# design.net
KiCad netlist of a schematic drawn in Altium Designer
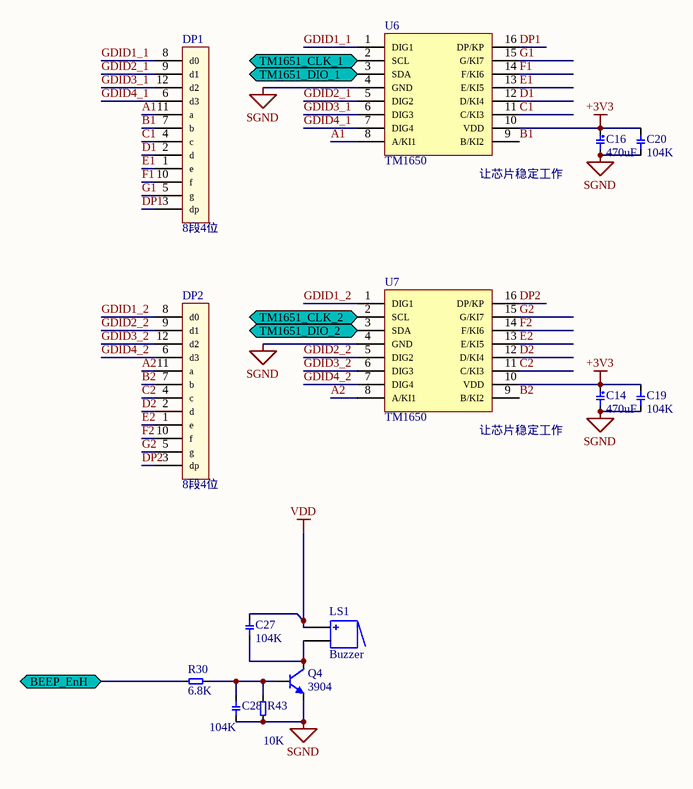
[diagram p0: 用户显示.SchDoc]

(export (version "E")
  (design (tool "Eeschema 10.0.6"))
  (components
    (comp (ref "C14")
      (value "470uF")
      (footprint "电容卧P2.54-D6.3-H7")
      (description "极性电容")
      (fields (field (name "PUBLISHER") "Altium Limited"))
      (libsource (lib "Miscellaneous Devices") (part "Cap Pol"))
    )
    (comp (ref "C16")
      (value "470uF")
      (footprint "电容卧P2.54-D6.3-H7")
      (description "极性电容")
      (fields (field (name "PUBLISHER") "Altium Limited"))
      (libsource (lib "Miscellaneous Devices") (part "Cap Pol"))
    )
    (comp (ref "C19")
      (value "104K")
      (footprint "0603")
      (description "电容")
      (fields (field (name "PUBLISHER") "Altium Limited"))
      (libsource (lib "Miscellaneous Devices") (part "Cap"))
    )
    (comp (ref "C20")
      (value "104K")
      (footprint "0603")
      (description "电容")
      (fields (field (name "PUBLISHER") "Altium Limited"))
      (libsource (lib "Miscellaneous Devices") (part "Cap"))
    )
    (comp (ref "C27")
      (value "104K")
      (footprint "0603")
      (description "电容")
      (fields (field (name "PUBLISHER") "Altium Limited"))
      (libsource (lib "Miscellaneous Devices") (part "Cap"))
    )
    (comp (ref "C28")
      (value "104K")
      (footprint "0603")
      (description "电容")
      (fields (field (name "PUBLISHER") "Altium Limited"))
      (libsource (lib "Miscellaneous Devices") (part "Cap"))
    )
    (comp (ref "DP1")
      (value "8段4位")
      (footprint "数码管0.36英寸")
      (description "数码管4位共阴")
      (libsource (lib "Miscellaneous Devices") (part "数码管4位"))
    )
    (comp (ref "DP2")
      (value "8段4位")
      (footprint "数码管0.36英寸")
      (description "数码管4位共阴")
      (libsource (lib "Miscellaneous Devices") (part "数码管4位"))
    )
    (comp (ref "LS1")
      (value "Buzzer")
      (footprint "蜂鸣器12-95")
      (description "Magnetic Transducer Buzzer")
      (fields (field (name "PUBLISHER") "Altium Limited"))
      (libsource (lib "Miscellaneous Devices") (part "蜂鸣器Buzzer"))
    )
    (comp (ref "Q4")
      (value "3904")
      (footprint "SOT-23-3L")
      (description "三极管")
      (fields (field (name "PUBLISHER") "Altium Limited"))
      (libsource (lib "Miscellaneous Devices") (part "transistor NPN"))
    )
    (comp (ref "R30")
      (value "6.8K")
      (footprint "0603")
      (description "电阻")
      (fields (field (name "PUBLISHER") "Altium Limited"))
      (libsource (lib "Miscellaneous Devices") (part "Res1"))
    )
    (comp (ref "R43")
      (value "10K")
      (footprint "0603")
      (description "电阻")
      (fields (field (name "PUBLISHER") "Altium Limited"))
      (libsource (lib "Miscellaneous Devices") (part "Res1"))
    )
    (comp (ref "U6")
      (value "TM1650")
      (footprint "SOIC16_39MM")
      (description "数码管驱动IC")
      (libsource (lib "Miscellaneous Devices") (part "TM1650"))
    )
    (comp (ref "U7")
      (value "TM1650")
      (footprint "SOIC16_39MM")
      (description "数码管驱动IC")
      (libsource (lib "Miscellaneous Devices") (part "TM1650"))
    )
  )
  (nets
    (net (code "1") (name "+3V3") (class "Default")
      (node (ref "C14") (pin "1") (pinfunction "1_1") (pintype "passive"))
      (node (ref "C16") (pin "1") (pinfunction "1_1") (pintype "passive"))
      (node (ref "C19") (pin "2") (pinfunction "2_2") (pintype "passive"))
      (node (ref "C20") (pin "2") (pinfunction "2_2") (pintype "passive"))
      (node (ref "U6") (pin "10") (pinfunction "VDD_10") (pintype "passive"))
      (node (ref "U7") (pin "10") (pinfunction "VDD_10") (pintype "passive"))
    )
    (net (code "2") (name "/A1") (class "Default")
      (node (ref "DP1") (pin "11") (pinfunction "a_11") (pintype "passive"))
      (node (ref "U6") (pin "8") (pinfunction "A/KI1_8") (pintype "passive"))
    )
    (net (code "3") (name "/A2") (class "Default")
      (node (ref "DP2") (pin "11") (pinfunction "a_11") (pintype "passive"))
      (node (ref "U7") (pin "8") (pinfunction "A/KI1_8") (pintype "passive"))
    )
    (net (code "4") (name "/B1") (class "Default")
      (node (ref "DP1") (pin "7") (pinfunction "b_7") (pintype "passive"))
      (node (ref "U6") (pin "9") (pinfunction "B/KI2_9") (pintype "passive"))
    )
    (net (code "5") (name "/B2") (class "Default")
      (node (ref "DP2") (pin "7") (pinfunction "b_7") (pintype "passive"))
      (node (ref "U7") (pin "9") (pinfunction "B/KI2_9") (pintype "passive"))
    )
    (net (code "6") (name "/BEEP_EnH") (class "Default")
      (node (ref "R30") (pin "1") (pinfunction "1_1") (pintype "passive"))
    )
    (net (code "7") (name "/C1") (class "Default")
      (node (ref "DP1") (pin "4") (pinfunction "c_4") (pintype "passive"))
      (node (ref "U6") (pin "11") (pinfunction "C/KI3_11") (pintype "passive"))
    )
    (net (code "8") (name "/C2") (class "Default")
      (node (ref "DP2") (pin "4") (pinfunction "c_4") (pintype "passive"))
      (node (ref "U7") (pin "11") (pinfunction "C/KI3_11") (pintype "passive"))
    )
    (net (code "9") (name "/D1") (class "Default")
      (node (ref "DP1") (pin "2") (pinfunction "d_2") (pintype "passive"))
      (node (ref "U6") (pin "12") (pinfunction "D/KI4_12") (pintype "passive"))
    )
    (net (code "10") (name "/D2") (class "Default")
      (node (ref "DP2") (pin "2") (pinfunction "d_2") (pintype "passive"))
      (node (ref "U7") (pin "12") (pinfunction "D/KI4_12") (pintype "passive"))
    )
    (net (code "11") (name "/DP1") (class "Default")
      (node (ref "DP1") (pin "3") (pinfunction "dp_3") (pintype "passive"))
      (node (ref "U6") (pin "16") (pinfunction "DP/KP_16") (pintype "passive"))
    )
    (net (code "12") (name "/DP2") (class "Default")
      (node (ref "DP2") (pin "3") (pinfunction "dp_3") (pintype "passive"))
      (node (ref "U7") (pin "16") (pinfunction "DP/KP_16") (pintype "passive"))
    )
    (net (code "13") (name "/E1") (class "Default")
      (node (ref "DP1") (pin "1") (pinfunction "e_1") (pintype "passive"))
      (node (ref "U6") (pin "13") (pinfunction "E/KI5_13") (pintype "passive"))
    )
    (net (code "14") (name "/E2") (class "Default")
      (node (ref "DP2") (pin "1") (pinfunction "e_1") (pintype "passive"))
      (node (ref "U7") (pin "13") (pinfunction "E/KI5_13") (pintype "passive"))
    )
    (net (code "15") (name "/F1") (class "Default")
      (node (ref "DP1") (pin "10") (pinfunction "f_10") (pintype "passive"))
      (node (ref "U6") (pin "14") (pinfunction "F/KI6_14") (pintype "passive"))
    )
    (net (code "16") (name "/F2") (class "Default")
      (node (ref "DP2") (pin "10") (pinfunction "f_10") (pintype "passive"))
      (node (ref "U7") (pin "14") (pinfunction "F/KI6_14") (pintype "passive"))
    )
    (net (code "17") (name "/G1") (class "Default")
      (node (ref "DP1") (pin "5") (pinfunction "g_5") (pintype "passive"))
      (node (ref "U6") (pin "15") (pinfunction "G/KI7_15") (pintype "passive"))
    )
    (net (code "18") (name "/G2") (class "Default")
      (node (ref "DP2") (pin "5") (pinfunction "g_5") (pintype "passive"))
      (node (ref "U7") (pin "15") (pinfunction "G/KI7_15") (pintype "passive"))
    )
    (net (code "19") (name "/GDID1_1") (class "Default")
      (node (ref "DP1") (pin "8") (pinfunction "d0_8") (pintype "passive"))
      (node (ref "U6") (pin "1") (pinfunction "DIG1_1") (pintype "passive"))
    )
    (net (code "20") (name "/GDID1_2") (class "Default")
      (node (ref "DP2") (pin "8") (pinfunction "d0_8") (pintype "passive"))
      (node (ref "U7") (pin "1") (pinfunction "DIG1_1") (pintype "passive"))
    )
    (net (code "21") (name "/GDID2_1") (class "Default")
      (node (ref "DP1") (pin "9") (pinfunction "d1_9") (pintype "tri_state"))
      (node (ref "U6") (pin "5") (pinfunction "DIG2_5") (pintype "passive"))
    )
    (net (code "22") (name "/GDID2_2") (class "Default")
      (node (ref "DP2") (pin "9") (pinfunction "d1_9") (pintype "tri_state"))
      (node (ref "U7") (pin "5") (pinfunction "DIG2_5") (pintype "passive"))
    )
    (net (code "23") (name "/GDID3_1") (class "Default")
      (node (ref "DP1") (pin "12") (pinfunction "d2_12") (pintype "passive"))
      (node (ref "U6") (pin "6") (pinfunction "DIG3_6") (pintype "passive"))
    )
    (net (code "24") (name "/GDID3_2") (class "Default")
      (node (ref "DP2") (pin "12") (pinfunction "d2_12") (pintype "passive"))
      (node (ref "U7") (pin "6") (pinfunction "DIG3_6") (pintype "passive"))
    )
    (net (code "25") (name "/GDID4_1") (class "Default")
      (node (ref "DP1") (pin "6") (pinfunction "d3_6") (pintype "passive"))
      (node (ref "U6") (pin "7") (pinfunction "DIG4_7") (pintype "passive"))
    )
    (net (code "26") (name "/GDID4_2") (class "Default")
      (node (ref "DP2") (pin "6") (pinfunction "d3_6") (pintype "passive"))
      (node (ref "U7") (pin "7") (pinfunction "DIG4_7") (pintype "passive"))
    )
    (net (code "27") (name "/TM1651_CLK_1") (class "Default")
      (node (ref "U6") (pin "2") (pinfunction "SCL_2") (pintype "passive"))
    )
    (net (code "28") (name "/TM1651_CLK_2") (class "Default")
      (node (ref "U7") (pin "2") (pinfunction "SCL_2") (pintype "passive"))
    )
    (net (code "29") (name "/TM1651_DIO_1") (class "Default")
      (node (ref "U6") (pin "3") (pinfunction "SDA_3") (pintype "passive"))
    )
    (net (code "30") (name "/TM1651_DIO_2") (class "Default")
      (node (ref "U7") (pin "3") (pinfunction "SDA_3") (pintype "passive"))
    )
    (net (code "31") (name "Net-(Q4-B)") (class "Default")
      (node (ref "C28") (pin "2") (pinfunction "2_2") (pintype "passive"))
      (node (ref "Q4") (pin "1") (pinfunction "B_1") (pintype "passive"))
      (node (ref "R30") (pin "2") (pinfunction "2_2") (pintype "passive"))
      (node (ref "R43") (pin "2") (pinfunction "2_2") (pintype "passive"))
    )
    (net (code "32") (name "Net-(Q4-C)") (class "Default")
      (node (ref "C27") (pin "1") (pinfunction "1_1") (pintype "passive"))
      (node (ref "LS1") (pin "2") (pinfunction "2_2") (pintype "passive"))
      (node (ref "Q4") (pin "3") (pinfunction "C_3") (pintype "passive"))
    )
    (net (code "33") (name "SGND") (class "Default")
      (node (ref "C14") (pin "2") (pinfunction "2_2") (pintype "passive"))
      (node (ref "C16") (pin "2") (pinfunction "2_2") (pintype "passive"))
      (node (ref "C19") (pin "1") (pinfunction "1_1") (pintype "passive"))
      (node (ref "C20") (pin "1") (pinfunction "1_1") (pintype "passive"))
      (node (ref "C28") (pin "1") (pinfunction "1_1") (pintype "passive"))
      (node (ref "Q4") (pin "2") (pinfunction "E_2") (pintype "passive"))
      (node (ref "R43") (pin "1") (pinfunction "1_1") (pintype "passive"))
      (node (ref "U6") (pin "4") (pinfunction "GND_4") (pintype "passive"))
      (node (ref "U7") (pin "4") (pinfunction "GND_4") (pintype "passive"))
    )
    (net (code "34") (name "VDD") (class "Default")
      (node (ref "C27") (pin "2") (pinfunction "2_2") (pintype "passive"))
      (node (ref "LS1") (pin "1") (pinfunction "1_1") (pintype "passive"))
    )
  )
)
